# dummy_load.net
KiCad netlist of a schematic drawn in EAGLE
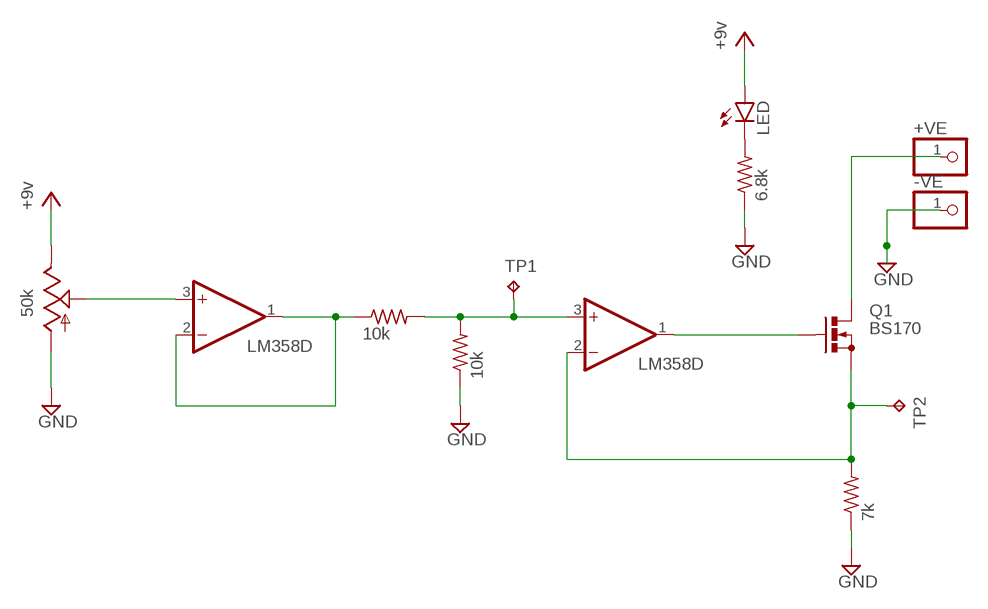
[diagram p0: schematic, sheet 1]

(export (version "E")
  (design (tool "Eeschema 10.0.6"))
  (components
    (comp (ref "+VE")
      (value "PINHD-1X1")
      (footprint "eagle-import:1X01")
      (libsource (lib "eagle-import") (part "PINHD-1X1"))
    )
    (comp (ref "-VE")
      (value "PINHD-1X1")
      (footprint "eagle-import:1X01")
      (libsource (lib "eagle-import") (part "PINHD-1X1"))
    )
    (comp (ref "IC1")
      (value "LM358D")
      (footprint "eagle-import:SO08")
      (libsource (lib "eagle-import") (part "LM358D"))
    )
    (comp (ref "IC2")
      (value "LM358D")
      (footprint "eagle-import:SO08")
      (libsource (lib "eagle-import") (part "LM358D"))
    )
    (comp (ref "LED")
      (value "LED5MM")
      (footprint "eagle-import:LED5MM")
      (libsource (lib "eagle-import") (part "LED5MM"))
    )
    (comp (ref "Q1")
      (value "BS170")
      (footprint "eagle-import:SOT54E")
      (libsource (lib "eagle-import") (part "BS170"))
    )
    (comp (ref "R1")
      (value "10k")
      (footprint "eagle-import:0204_7")
      (libsource (lib "eagle-import") (part "R-US_0204/7"))
    )
    (comp (ref "R2")
      (value "10k")
      (footprint "eagle-import:0204_7")
      (libsource (lib "eagle-import") (part "R-US_0204/7"))
    )
    (comp (ref "R3")
      (value "7k")
      (footprint "eagle-import:0204_7")
      (libsource (lib "eagle-import") (part "R-US_0204/7"))
    )
    (comp (ref "R4")
      (value "6.8k")
      (footprint "eagle-import:0204_7")
      (libsource (lib "eagle-import") (part "R-US_0204/7"))
    )
    (comp (ref "R5")
      (value "50k")
      (footprint "eagle-import:B25P")
      (libsource (lib "eagle-import") (part "TRIM_US-B25P"))
    )
    (comp (ref "TP1")
      (value "TPB1,27")
      (footprint "eagle-import:B1,27")
      (libsource (lib "eagle-import") (part "TPB1,27"))
    )
    (comp (ref "TP2")
      (value "TPB1,27")
      (footprint "eagle-import:B1,27")
      (libsource (lib "eagle-import") (part "TPB1,27"))
    )
  )
  (nets
    (net (code "1") (name "+9v") (class "Default")
      (node (ref "LED") (pin "A") (pinfunction "A_A") (pintype "passive"))
      (node (ref "R5") (pin "E") (pinfunction "E_E") (pintype "passive"))
    )
    (net (code "2") (name "GND") (class "Default")
      (node (ref "-VE") (pin "1") (pinfunction "1_1") (pintype "passive"))
      (node (ref "R2") (pin "1") (pinfunction "1_1") (pintype "passive"))
      (node (ref "R3") (pin "1") (pinfunction "1_1") (pintype "passive"))
      (node (ref "R4") (pin "1") (pinfunction "1_1") (pintype "passive"))
      (node (ref "R5") (pin "A") (pinfunction "A_A") (pintype "passive"))
    )
    (net (code "3") (name "Net-(+VE-Pad1)") (class "Default")
      (node (ref "+VE") (pin "1") (pinfunction "1_1") (pintype "passive"))
      (node (ref "Q1") (pin "D") (pinfunction "D_D") (pintype "passive"))
    )
    (net (code "4") (name "Net-(IC1A-+IN)") (class "Default")
      (node (ref "IC1") (pin "3") (pinfunction "+IN_3") (pintype "input"))
      (node (ref "R5") (pin "S") (pinfunction "S_S") (pintype "passive"))
    )
    (net (code "5") (name "Net-(IC1A--IN)") (class "Default")
      (node (ref "IC1") (pin "1") (pinfunction "OUT_1") (pintype "output"))
      (node (ref "IC1") (pin "2") (pinfunction "-IN_2") (pintype "input"))
      (node (ref "R1") (pin "1") (pinfunction "1_1") (pintype "passive"))
    )
    (net (code "6") (name "Net-(IC2A-+IN)") (class "Default")
      (node (ref "IC2") (pin "3") (pinfunction "+IN_3") (pintype "input"))
      (node (ref "R1") (pin "2") (pinfunction "2_2") (pintype "passive"))
      (node (ref "R2") (pin "2") (pinfunction "2_2") (pintype "passive"))
      (node (ref "TP1") (pin "TP") (pinfunction "TP_TP") (pintype "input"))
    )
    (net (code "7") (name "Net-(IC2A--IN)") (class "Default")
      (node (ref "IC2") (pin "2") (pinfunction "-IN_2") (pintype "input"))
      (node (ref "Q1") (pin "S") (pinfunction "S_S") (pintype "passive"))
      (node (ref "R3") (pin "2") (pinfunction "2_2") (pintype "passive"))
      (node (ref "TP2") (pin "TP") (pinfunction "TP_TP") (pintype "input"))
    )
    (net (code "8") (name "Net-(IC2A-OUT)") (class "Default")
      (node (ref "IC2") (pin "1") (pinfunction "OUT_1") (pintype "output"))
      (node (ref "Q1") (pin "G") (pinfunction "G_G") (pintype "passive"))
    )
    (net (code "9") (name "Net-(LED-C)") (class "Default")
      (node (ref "LED") (pin "K") (pinfunction "C_K") (pintype "passive"))
      (node (ref "R4") (pin "2") (pinfunction "2_2") (pintype "passive"))
    )
  )
)
